# SWITCHES.net
KiCad netlist of a schematic drawn in Altium Designer
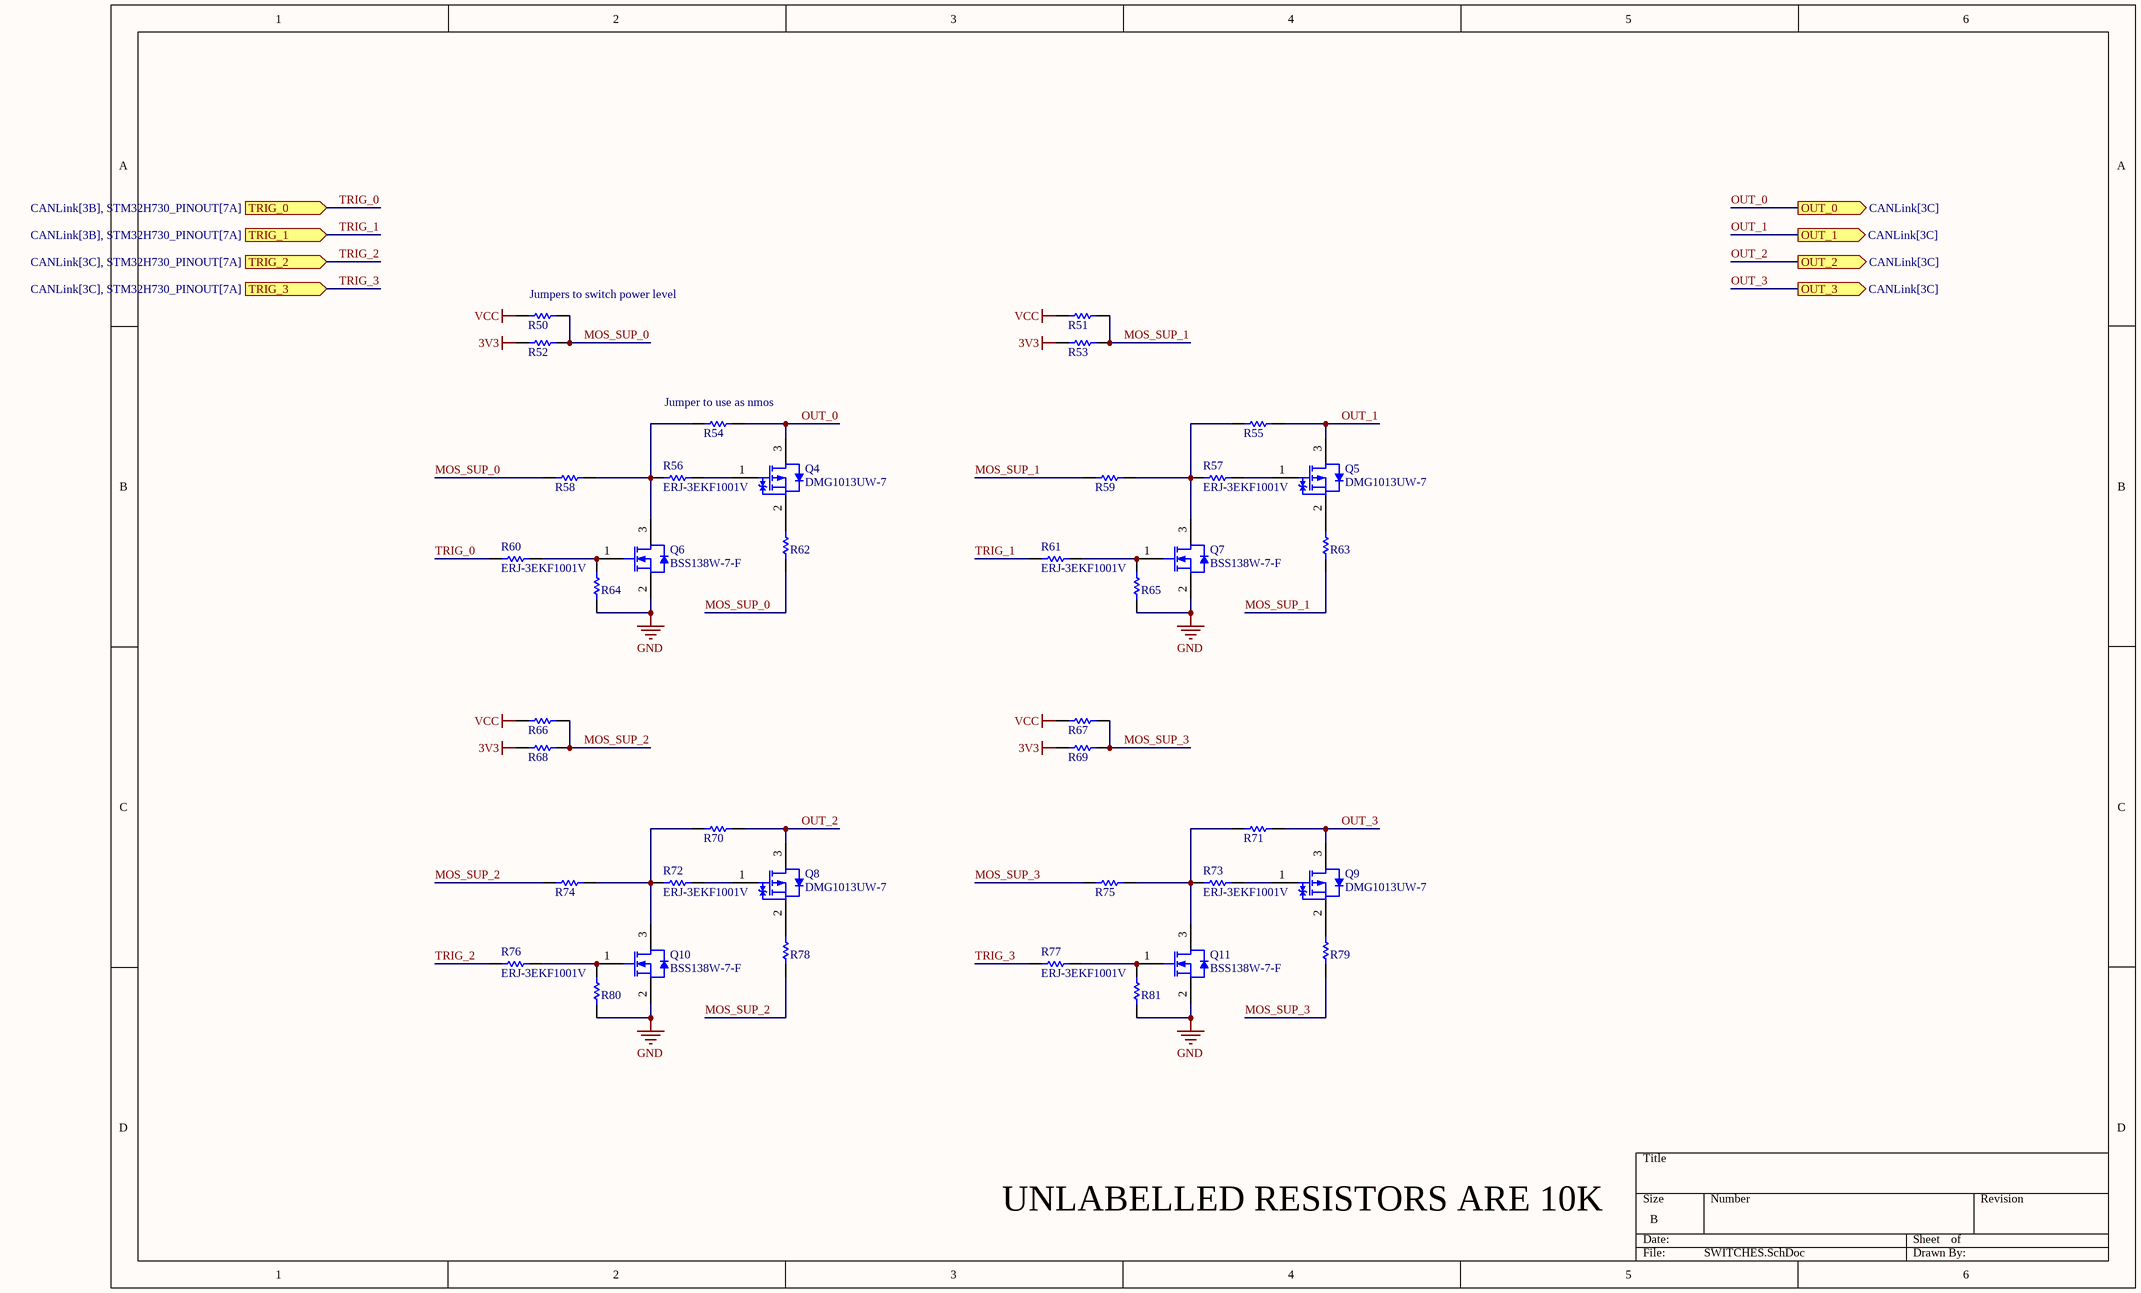
[diagram p0: SWITCHES.SchDoc]

(export (version "E")
  (design (tool "Eeschema 10.0.6"))
  (components
    (comp (ref "Q4")
      (value "DMG1013UW-7")
      (footprint "DIOD-SOT323-3_V")
      (fields (field (name "MANUFACTURER") "Diodes Inc"))
      (libsource (lib "Altium Content Vault") (part "PEMOS-GSD-3_C"))
    )
    (comp (ref "Q5")
      (value "DMG1013UW-7")
      (footprint "DIOD-SOT323-3_V")
      (fields (field (name "MANUFACTURER") "Diodes Inc"))
      (libsource (lib "Altium Content Vault") (part "PEMOS-GSD-3_C"))
    )
    (comp (ref "Q6")
      (value "BSS138W-7-F")
      (footprint "DIOD-SOT323-3_V")
      (fields (field (name "MANUFACTURER") "DiodesIncorporated"))
      (libsource (lib "Altium Content Vault") (part "NEMOS-GSD-3"))
    )
    (comp (ref "Q7")
      (value "BSS138W-7-F")
      (footprint "DIOD-SOT323-3_V")
      (fields (field (name "MANUFACTURER") "DiodesIncorporated"))
      (libsource (lib "Altium Content Vault") (part "NEMOS-GSD-3"))
    )
    (comp (ref "Q8")
      (value "DMG1013UW-7")
      (footprint "DIOD-SOT323-3_V")
      (fields (field (name "MANUFACTURER") "Diodes Inc"))
      (libsource (lib "Altium Content Vault") (part "PEMOS-GSD-3_C"))
    )
    (comp (ref "Q9")
      (value "DMG1013UW-7")
      (footprint "DIOD-SOT323-3_V")
      (fields (field (name "MANUFACTURER") "Diodes Inc"))
      (libsource (lib "Altium Content Vault") (part "PEMOS-GSD-3_C"))
    )
    (comp (ref "Q10")
      (value "BSS138W-7-F")
      (footprint "DIOD-SOT323-3_V")
      (fields (field (name "MANUFACTURER") "DiodesIncorporated"))
      (libsource (lib "Altium Content Vault") (part "NEMOS-GSD-3"))
    )
    (comp (ref "Q11")
      (value "BSS138W-7-F")
      (footprint "DIOD-SOT323-3_V")
      (fields (field (name "MANUFACTURER") "DiodesIncorporated"))
      (libsource (lib "Altium Content Vault") (part "NEMOS-GSD-3"))
    )
    (comp (ref "R50")
      (value "0402 JUMPER 0 OHM")
      (footprint "RESC1005X40X25NL05T05")
      (description "READ THE NAME")
      (libsource (lib "uORocketry Hardware") (part "RES"))
    )
    (comp (ref "R51")
      (value "0402 JUMPER 0 OHM")
      (footprint "RESC1005X40X25NL05T05")
      (description "READ THE NAME")
      (libsource (lib "uORocketry Hardware") (part "RES"))
    )
    (comp (ref "R52")
      (value "0402 JUMPER 0 OHM")
      (footprint "RESC1005X40X25NL05T05")
      (description "READ THE NAME")
      (libsource (lib "uORocketry Hardware") (part "RES"))
    )
    (comp (ref "R53")
      (value "0402 JUMPER 0 OHM")
      (footprint "RESC1005X40X25NL05T05")
      (description "READ THE NAME")
      (libsource (lib "uORocketry Hardware") (part "RES"))
    )
    (comp (ref "R54")
      (value "0402 JUMPER 0 OHM")
      (footprint "RESC1005X40X25NL05T05")
      (description "READ THE NAME")
      (libsource (lib "uORocketry Hardware") (part "RES"))
    )
    (comp (ref "R55")
      (value "0402 JUMPER 0 OHM")
      (footprint "RESC1005X40X25NL05T05")
      (description "READ THE NAME")
      (libsource (lib "uORocketry Hardware") (part "RES"))
    )
    (comp (ref "R56")
      (value "ERJ-3EKF1001V")
      (footprint "RESC1608X55X30LL15T15")
      (fields (field (name "MANUFACTURER") "Panasonic"))
      (libsource (lib "Altium Content Vault") (part "RES"))
    )
    (comp (ref "R57")
      (value "ERJ-3EKF1001V")
      (footprint "RESC1608X55X30LL15T15")
      (fields (field (name "MANUFACTURER") "Panasonic"))
      (libsource (lib "Altium Content Vault") (part "RES"))
    )
    (comp (ref "R58")
      (value "ERJ3EKF1002V")
      (footprint "RESC1609X55X30LL15T15")
      (description "Chip Resistor, 10 KOhm, +/- 1%, 0.1 W, -55 to 155 degC, 0603 (1608 Metric), RoHS, Tape and Reel")
      (fields (field (name "TOLERANCE") "1%") (field (name "MANUFACTURER") "Panasonic"))
      (libsource (lib "Altium Content Vault") (part "RES-2"))
    )
    (comp (ref "R59")
      (value "ERJ3EKF1002V")
      (footprint "RESC1609X55X30LL15T15")
      (description "Chip Resistor, 10 KOhm, +/- 1%, 0.1 W, -55 to 155 degC, 0603 (1608 Metric), RoHS, Tape and Reel")
      (fields (field (name "TOLERANCE") "1%") (field (name "MANUFACTURER") "Panasonic"))
      (libsource (lib "Altium Content Vault") (part "RES-2"))
    )
    (comp (ref "R60")
      (value "ERJ-3EKF1001V")
      (footprint "RESC1608X55X30LL15T15")
      (fields (field (name "MANUFACTURER") "Panasonic"))
      (libsource (lib "Altium Content Vault") (part "RES"))
    )
    (comp (ref "R61")
      (value "ERJ-3EKF1001V")
      (footprint "RESC1608X55X30LL15T15")
      (fields (field (name "MANUFACTURER") "Panasonic"))
      (libsource (lib "Altium Content Vault") (part "RES"))
    )
    (comp (ref "R62")
      (value "ERJ3EKF1002V")
      (footprint "RESC1609X55X30LL15T15")
      (description "Chip Resistor, 10 KOhm, +/- 1%, 0.1 W, -55 to 155 degC, 0603 (1608 Metric), RoHS, Tape and Reel")
      (fields (field (name "TOLERANCE") "1%") (field (name "MANUFACTURER") "Panasonic"))
      (libsource (lib "Altium Content Vault") (part "RES-2"))
    )
    (comp (ref "R63")
      (value "ERJ3EKF1002V")
      (footprint "RESC1609X55X30LL15T15")
      (description "Chip Resistor, 10 KOhm, +/- 1%, 0.1 W, -55 to 155 degC, 0603 (1608 Metric), RoHS, Tape and Reel")
      (fields (field (name "TOLERANCE") "1%") (field (name "MANUFACTURER") "Panasonic"))
      (libsource (lib "Altium Content Vault") (part "RES-2"))
    )
    (comp (ref "R64")
      (value "ERJ3EKF1002V")
      (footprint "RESC1609X55X30LL15T15")
      (description "Chip Resistor, 10 KOhm, +/- 1%, 0.1 W, -55 to 155 degC, 0603 (1608 Metric), RoHS, Tape and Reel")
      (fields (field (name "TOLERANCE") "1%") (field (name "MANUFACTURER") "Panasonic"))
      (libsource (lib "Altium Content Vault") (part "RES-2"))
    )
    (comp (ref "R65")
      (value "ERJ3EKF1002V")
      (footprint "RESC1609X55X30LL15T15")
      (description "Chip Resistor, 10 KOhm, +/- 1%, 0.1 W, -55 to 155 degC, 0603 (1608 Metric), RoHS, Tape and Reel")
      (fields (field (name "TOLERANCE") "1%") (field (name "MANUFACTURER") "Panasonic"))
      (libsource (lib "Altium Content Vault") (part "RES-2"))
    )
    (comp (ref "R66")
      (value "0402 JUMPER 0 OHM")
      (footprint "RESC1005X40X25NL05T05")
      (description "READ THE NAME")
      (libsource (lib "uORocketry Hardware") (part "RES"))
    )
    (comp (ref "R67")
      (value "0402 JUMPER 0 OHM")
      (footprint "RESC1005X40X25NL05T05")
      (description "READ THE NAME")
      (libsource (lib "uORocketry Hardware") (part "RES"))
    )
    (comp (ref "R68")
      (value "0402 JUMPER 0 OHM")
      (footprint "RESC1005X40X25NL05T05")
      (description "READ THE NAME")
      (libsource (lib "uORocketry Hardware") (part "RES"))
    )
    (comp (ref "R69")
      (value "0402 JUMPER 0 OHM")
      (footprint "RESC1005X40X25NL05T05")
      (description "READ THE NAME")
      (libsource (lib "uORocketry Hardware") (part "RES"))
    )
    (comp (ref "R70")
      (value "0402 JUMPER 0 OHM")
      (footprint "RESC1005X40X25NL05T05")
      (description "READ THE NAME")
      (libsource (lib "uORocketry Hardware") (part "RES"))
    )
    (comp (ref "R71")
      (value "0402 JUMPER 0 OHM")
      (footprint "RESC1005X40X25NL05T05")
      (description "READ THE NAME")
      (libsource (lib "uORocketry Hardware") (part "RES"))
    )
    (comp (ref "R72")
      (value "ERJ-3EKF1001V")
      (footprint "RESC1608X55X30LL15T15")
      (fields (field (name "MANUFACTURER") "Panasonic"))
      (libsource (lib "Altium Content Vault") (part "RES"))
    )
    (comp (ref "R73")
      (value "ERJ-3EKF1001V")
      (footprint "RESC1608X55X30LL15T15")
      (fields (field (name "MANUFACTURER") "Panasonic"))
      (libsource (lib "Altium Content Vault") (part "RES"))
    )
    (comp (ref "R74")
      (value "ERJ3EKF1002V")
      (footprint "RESC1609X55X30LL15T15")
      (description "Chip Resistor, 10 KOhm, +/- 1%, 0.1 W, -55 to 155 degC, 0603 (1608 Metric), RoHS, Tape and Reel")
      (fields (field (name "TOLERANCE") "1%") (field (name "MANUFACTURER") "Panasonic"))
      (libsource (lib "Altium Content Vault") (part "RES-2"))
    )
    (comp (ref "R75")
      (value "ERJ3EKF1002V")
      (footprint "RESC1609X55X30LL15T15")
      (description "Chip Resistor, 10 KOhm, +/- 1%, 0.1 W, -55 to 155 degC, 0603 (1608 Metric), RoHS, Tape and Reel")
      (fields (field (name "TOLERANCE") "1%") (field (name "MANUFACTURER") "Panasonic"))
      (libsource (lib "Altium Content Vault") (part "RES-2"))
    )
    (comp (ref "R76")
      (value "ERJ-3EKF1001V")
      (footprint "RESC1608X55X30LL15T15")
      (fields (field (name "MANUFACTURER") "Panasonic"))
      (libsource (lib "Altium Content Vault") (part "RES"))
    )
    (comp (ref "R77")
      (value "ERJ-3EKF1001V")
      (footprint "RESC1608X55X30LL15T15")
      (fields (field (name "MANUFACTURER") "Panasonic"))
      (libsource (lib "Altium Content Vault") (part "RES"))
    )
    (comp (ref "R78")
      (value "ERJ3EKF1002V")
      (footprint "RESC1609X55X30LL15T15")
      (description "Chip Resistor, 10 KOhm, +/- 1%, 0.1 W, -55 to 155 degC, 0603 (1608 Metric), RoHS, Tape and Reel")
      (fields (field (name "TOLERANCE") "1%") (field (name "MANUFACTURER") "Panasonic"))
      (libsource (lib "Altium Content Vault") (part "RES-2"))
    )
    (comp (ref "R79")
      (value "ERJ3EKF1002V")
      (footprint "RESC1609X55X30LL15T15")
      (description "Chip Resistor, 10 KOhm, +/- 1%, 0.1 W, -55 to 155 degC, 0603 (1608 Metric), RoHS, Tape and Reel")
      (fields (field (name "TOLERANCE") "1%") (field (name "MANUFACTURER") "Panasonic"))
      (libsource (lib "Altium Content Vault") (part "RES-2"))
    )
    (comp (ref "R80")
      (value "ERJ3EKF1002V")
      (footprint "RESC1609X55X30LL15T15")
      (description "Chip Resistor, 10 KOhm, +/- 1%, 0.1 W, -55 to 155 degC, 0603 (1608 Metric), RoHS, Tape and Reel")
      (fields (field (name "TOLERANCE") "1%") (field (name "MANUFACTURER") "Panasonic"))
      (libsource (lib "Altium Content Vault") (part "RES-2"))
    )
    (comp (ref "R81")
      (value "ERJ3EKF1002V")
      (footprint "RESC1609X55X30LL15T15")
      (description "Chip Resistor, 10 KOhm, +/- 1%, 0.1 W, -55 to 155 degC, 0603 (1608 Metric), RoHS, Tape and Reel")
      (fields (field (name "TOLERANCE") "1%") (field (name "MANUFACTURER") "Panasonic"))
      (libsource (lib "Altium Content Vault") (part "RES-2"))
    )
  )
  (nets
    (net (code "1") (name "/MOS_SUP_0") (class "Default")
      (node (ref "R50") (pin "2") (pinfunction "2_2") (pintype "passive"))
      (node (ref "R52") (pin "2") (pinfunction "2_2") (pintype "passive"))
      (node (ref "R58") (pin "2") (pinfunction "2_2") (pintype "passive"))
      (node (ref "R62") (pin "1") (pinfunction "1_1") (pintype "passive"))
    )
    (net (code "2") (name "/MOS_SUP_1") (class "Default")
      (node (ref "R51") (pin "2") (pinfunction "2_2") (pintype "passive"))
      (node (ref "R53") (pin "2") (pinfunction "2_2") (pintype "passive"))
      (node (ref "R59") (pin "2") (pinfunction "2_2") (pintype "passive"))
      (node (ref "R63") (pin "1") (pinfunction "1_1") (pintype "passive"))
    )
    (net (code "3") (name "/MOS_SUP_2") (class "Default")
      (node (ref "R66") (pin "2") (pinfunction "2_2") (pintype "passive"))
      (node (ref "R68") (pin "2") (pinfunction "2_2") (pintype "passive"))
      (node (ref "R74") (pin "2") (pinfunction "2_2") (pintype "passive"))
      (node (ref "R78") (pin "1") (pinfunction "1_1") (pintype "passive"))
    )
    (net (code "4") (name "/MOS_SUP_3") (class "Default")
      (node (ref "R67") (pin "2") (pinfunction "2_2") (pintype "passive"))
      (node (ref "R69") (pin "2") (pinfunction "2_2") (pintype "passive"))
      (node (ref "R75") (pin "2") (pinfunction "2_2") (pintype "passive"))
      (node (ref "R79") (pin "1") (pinfunction "1_1") (pintype "passive"))
    )
    (net (code "5") (name "/OUT_0") (class "Default")
      (node (ref "Q4") (pin "3") (pinfunction "D_3") (pintype "passive"))
      (node (ref "R54") (pin "2") (pinfunction "2_2") (pintype "passive"))
    )
    (net (code "6") (name "/OUT_1") (class "Default")
      (node (ref "Q5") (pin "3") (pinfunction "D_3") (pintype "passive"))
      (node (ref "R55") (pin "2") (pinfunction "2_2") (pintype "passive"))
    )
    (net (code "7") (name "/OUT_2") (class "Default")
      (node (ref "Q8") (pin "3") (pinfunction "D_3") (pintype "passive"))
      (node (ref "R70") (pin "2") (pinfunction "2_2") (pintype "passive"))
    )
    (net (code "8") (name "/OUT_3") (class "Default")
      (node (ref "Q9") (pin "3") (pinfunction "D_3") (pintype "passive"))
      (node (ref "R71") (pin "2") (pinfunction "2_2") (pintype "passive"))
    )
    (net (code "9") (name "/TRIG_0") (class "Default")
      (node (ref "R60") (pin "1") (pinfunction "1_1") (pintype "passive"))
    )
    (net (code "10") (name "/TRIG_1") (class "Default")
      (node (ref "R61") (pin "1") (pinfunction "1_1") (pintype "passive"))
    )
    (net (code "11") (name "/TRIG_2") (class "Default")
      (node (ref "R76") (pin "1") (pinfunction "1_1") (pintype "passive"))
    )
    (net (code "12") (name "/TRIG_3") (class "Default")
      (node (ref "R77") (pin "1") (pinfunction "1_1") (pintype "passive"))
    )
    (net (code "13") (name "3V3") (class "Default")
      (node (ref "R52") (pin "1") (pinfunction "1_1") (pintype "passive"))
      (node (ref "R53") (pin "1") (pinfunction "1_1") (pintype "passive"))
      (node (ref "R68") (pin "1") (pinfunction "1_1") (pintype "passive"))
      (node (ref "R69") (pin "1") (pinfunction "1_1") (pintype "passive"))
    )
    (net (code "14") (name "GND") (class "Default")
      (node (ref "Q10") (pin "2") (pinfunction "S_2") (pintype "passive"))
      (node (ref "Q11") (pin "2") (pinfunction "S_2") (pintype "passive"))
      (node (ref "Q6") (pin "2") (pinfunction "S_2") (pintype "passive"))
      (node (ref "Q7") (pin "2") (pinfunction "S_2") (pintype "passive"))
      (node (ref "R64") (pin "1") (pinfunction "1_1") (pintype "passive"))
      (node (ref "R65") (pin "1") (pinfunction "1_1") (pintype "passive"))
      (node (ref "R80") (pin "1") (pinfunction "1_1") (pintype "passive"))
      (node (ref "R81") (pin "1") (pinfunction "1_1") (pintype "passive"))
    )
    (net (code "15") (name "Net-(Q4-G)") (class "Default")
      (node (ref "Q4") (pin "1") (pinfunction "G_1") (pintype "passive"))
      (node (ref "R56") (pin "2") (pinfunction "2_2") (pintype "passive"))
    )
    (net (code "16") (name "Net-(Q4-S)") (class "Default")
      (node (ref "Q4") (pin "2") (pinfunction "S_2") (pintype "passive"))
      (node (ref "R62") (pin "2") (pinfunction "2_2") (pintype "passive"))
    )
    (net (code "17") (name "Net-(Q5-G)") (class "Default")
      (node (ref "Q5") (pin "1") (pinfunction "G_1") (pintype "passive"))
      (node (ref "R57") (pin "2") (pinfunction "2_2") (pintype "passive"))
    )
    (net (code "18") (name "Net-(Q5-S)") (class "Default")
      (node (ref "Q5") (pin "2") (pinfunction "S_2") (pintype "passive"))
      (node (ref "R63") (pin "2") (pinfunction "2_2") (pintype "passive"))
    )
    (net (code "19") (name "Net-(Q6-D)") (class "Default")
      (node (ref "Q6") (pin "3") (pinfunction "D_3") (pintype "passive"))
      (node (ref "R54") (pin "1") (pinfunction "1_1") (pintype "passive"))
      (node (ref "R56") (pin "1") (pinfunction "1_1") (pintype "passive"))
      (node (ref "R58") (pin "1") (pinfunction "1_1") (pintype "passive"))
    )
    (net (code "20") (name "Net-(Q6-G)") (class "Default")
      (node (ref "Q6") (pin "1") (pinfunction "G_1") (pintype "passive"))
      (node (ref "R60") (pin "2") (pinfunction "2_2") (pintype "passive"))
      (node (ref "R64") (pin "2") (pinfunction "2_2") (pintype "passive"))
    )
    (net (code "21") (name "Net-(Q7-D)") (class "Default")
      (node (ref "Q7") (pin "3") (pinfunction "D_3") (pintype "passive"))
      (node (ref "R55") (pin "1") (pinfunction "1_1") (pintype "passive"))
      (node (ref "R57") (pin "1") (pinfunction "1_1") (pintype "passive"))
      (node (ref "R59") (pin "1") (pinfunction "1_1") (pintype "passive"))
    )
    (net (code "22") (name "Net-(Q7-G)") (class "Default")
      (node (ref "Q7") (pin "1") (pinfunction "G_1") (pintype "passive"))
      (node (ref "R61") (pin "2") (pinfunction "2_2") (pintype "passive"))
      (node (ref "R65") (pin "2") (pinfunction "2_2") (pintype "passive"))
    )
    (net (code "23") (name "Net-(Q8-G)") (class "Default")
      (node (ref "Q8") (pin "1") (pinfunction "G_1") (pintype "passive"))
      (node (ref "R72") (pin "2") (pinfunction "2_2") (pintype "passive"))
    )
    (net (code "24") (name "Net-(Q8-S)") (class "Default")
      (node (ref "Q8") (pin "2") (pinfunction "S_2") (pintype "passive"))
      (node (ref "R78") (pin "2") (pinfunction "2_2") (pintype "passive"))
    )
    (net (code "25") (name "Net-(Q9-G)") (class "Default")
      (node (ref "Q9") (pin "1") (pinfunction "G_1") (pintype "passive"))
      (node (ref "R73") (pin "2") (pinfunction "2_2") (pintype "passive"))
    )
    (net (code "26") (name "Net-(Q9-S)") (class "Default")
      (node (ref "Q9") (pin "2") (pinfunction "S_2") (pintype "passive"))
      (node (ref "R79") (pin "2") (pinfunction "2_2") (pintype "passive"))
    )
    (net (code "27") (name "Net-(Q10-D)") (class "Default")
      (node (ref "Q10") (pin "3") (pinfunction "D_3") (pintype "passive"))
      (node (ref "R70") (pin "1") (pinfunction "1_1") (pintype "passive"))
      (node (ref "R72") (pin "1") (pinfunction "1_1") (pintype "passive"))
      (node (ref "R74") (pin "1") (pinfunction "1_1") (pintype "passive"))
    )
    (net (code "28") (name "Net-(Q10-G)") (class "Default")
      (node (ref "Q10") (pin "1") (pinfunction "G_1") (pintype "passive"))
      (node (ref "R76") (pin "2") (pinfunction "2_2") (pintype "passive"))
      (node (ref "R80") (pin "2") (pinfunction "2_2") (pintype "passive"))
    )
    (net (code "29") (name "Net-(Q11-D)") (class "Default")
      (node (ref "Q11") (pin "3") (pinfunction "D_3") (pintype "passive"))
      (node (ref "R71") (pin "1") (pinfunction "1_1") (pintype "passive"))
      (node (ref "R73") (pin "1") (pinfunction "1_1") (pintype "passive"))
      (node (ref "R75") (pin "1") (pinfunction "1_1") (pintype "passive"))
    )
    (net (code "30") (name "Net-(Q11-G)") (class "Default")
      (node (ref "Q11") (pin "1") (pinfunction "G_1") (pintype "passive"))
      (node (ref "R77") (pin "2") (pinfunction "2_2") (pintype "passive"))
      (node (ref "R81") (pin "2") (pinfunction "2_2") (pintype "passive"))
    )
    (net (code "31") (name "VCC") (class "Default")
      (node (ref "R50") (pin "1") (pinfunction "1_1") (pintype "passive"))
      (node (ref "R51") (pin "1") (pinfunction "1_1") (pintype "passive"))
      (node (ref "R66") (pin "1") (pinfunction "1_1") (pintype "passive"))
      (node (ref "R67") (pin "1") (pinfunction "1_1") (pintype "passive"))
    )
  )
)
